# driver_board.net
KiCad netlist of a schematic drawn in EAGLE
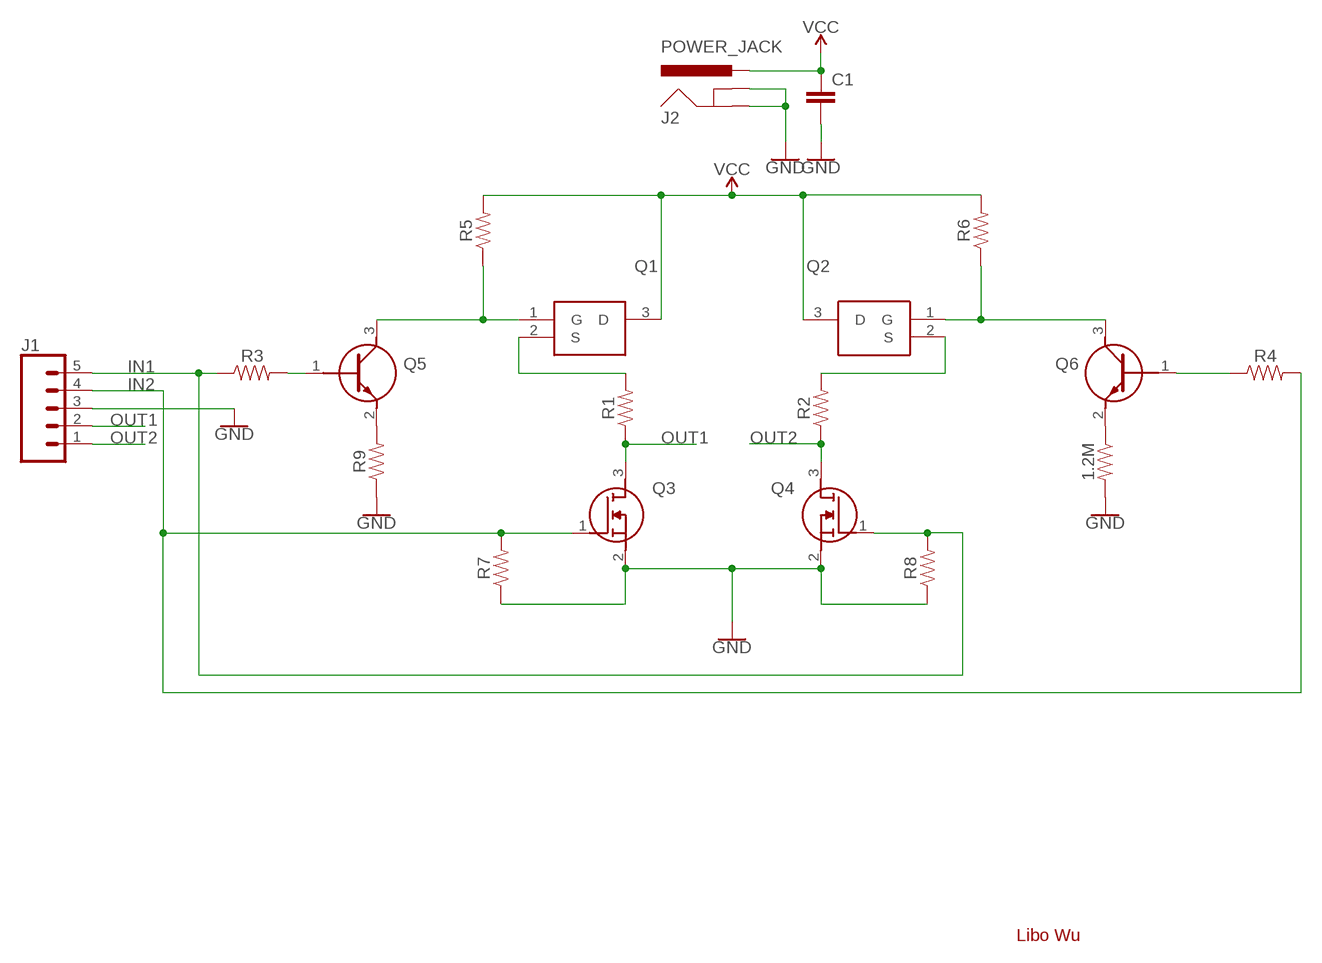
[diagram p0: schematic, sheet 1]

(export (version "E")
  (design (tool "Eeschema 10.0.6"))
  (components
    (comp (ref "C1")
      (value "10nF")
      (footprint "eagle-import:0603")
      (libsource (lib "eagle-import") (part "10NF-0603-50V-10%"))
    )
    (comp (ref "J1")
      (value "CONN_05")
      (footprint "eagle-import:1X05")
      (libsource (lib "eagle-import") (part "CONN_05"))
    )
    (comp (ref "J2")
      (value "POWER_JACK")
      (footprint "eagle-import:POWER_JACK_PTH")
      (libsource (lib "eagle-import") (part "POWER_JACK"))
    )
    (comp (ref "Q1")
      (value "IRLML6401TRPBF")
      (footprint "eagle-import:SOT95P237X112-3N")
      (fields (field (name "MOUSER_PART_NUMBER") "942-IRLML6401TRPBF"))
      (libsource (lib "eagle-import") (part "IRLML6401TRPBF"))
    )
    (comp (ref "Q2")
      (value "IRLML6401TRPBF")
      (footprint "eagle-import:SOT95P237X112-3N")
      (fields (field (name "MOUSER_PART_NUMBER") "942-IRLML6401TRPBF"))
      (libsource (lib "eagle-import") (part "IRLML6401TRPBF"))
    )
    (comp (ref "Q3")
      (value "IRLML2502TRPBF")
      (footprint "eagle-import:SOT95P237X112-3N")
      (fields (field (name "MOUSER_PART_NUMBER") "942-IRLML2502TRPBF"))
      (libsource (lib "eagle-import") (part "IRLML2502TRPBF"))
    )
    (comp (ref "Q4")
      (value "IRLML2502TRPBF")
      (footprint "eagle-import:SOT95P237X112-3N")
      (fields (field (name "MOUSER_PART_NUMBER") "942-IRLML2502TRPBF"))
      (libsource (lib "eagle-import") (part "IRLML2502TRPBF"))
    )
    (comp (ref "Q5")
      (value "BCW66HQTA")
      (footprint "eagle-import:FMMT619TA")
      (fields (field (name "MOUSER_PART_NUMBER") "621-BCW66HQTA"))
      (libsource (lib "eagle-import") (part "BCW66HQTA"))
    )
    (comp (ref "Q6")
      (value "BCW66HQTA")
      (footprint "eagle-import:FMMT619TA")
      (fields (field (name "MOUSER_PART_NUMBER") "621-BCW66HQTA"))
      (libsource (lib "eagle-import") (part "BCW66HQTA"))
    )
    (comp (ref "R1")
      (value "1.2M")
      (footprint "eagle-import:0603")
      (libsource (lib "eagle-import") (part "1.2MOHM-0603-1/10W-1%"))
    )
    (comp (ref "R2")
      (value "1.2M")
      (footprint "eagle-import:0603")
      (libsource (lib "eagle-import") (part "1.2MOHM-0603-1/10W-1%"))
    )
    (comp (ref "R3")
      (value "1.2M")
      (footprint "eagle-import:0603")
      (libsource (lib "eagle-import") (part "1.2MOHM-0603-1/10W-1%"))
    )
    (comp (ref "R4")
      (value "1.2M")
      (footprint "eagle-import:0603")
      (libsource (lib "eagle-import") (part "1.2MOHM-0603-1/10W-1%"))
    )
    (comp (ref "R5")
      (value "1.2M")
      (footprint "eagle-import:0603")
      (libsource (lib "eagle-import") (part "1.2MOHM-0603-1/10W-1%"))
    )
    (comp (ref "R6")
      (value "1.2M")
      (footprint "eagle-import:0603")
      (libsource (lib "eagle-import") (part "1.2MOHM-0603-1/10W-1%"))
    )
    (comp (ref "R7")
      (value "1.2M")
      (footprint "eagle-import:0603")
      (libsource (lib "eagle-import") (part "1.2MOHM-0603-1/10W-1%"))
    )
    (comp (ref "R8")
      (value "1.2M")
      (footprint "eagle-import:0603")
      (libsource (lib "eagle-import") (part "1.2MOHM-0603-1/10W-1%"))
    )
    (comp (ref "R9")
      (value "1.2M")
      (footprint "eagle-import:0603")
      (libsource (lib "eagle-import") (part "1.2MOHM-0603-1/10W-1%"))
    )
    (comp (ref "R10")
      (value "1.2M")
      (footprint "eagle-import:0603")
      (libsource (lib "eagle-import") (part "1.2MOHM-0603-1/10W-1%"))
    )
  )
  (nets
    (net (code "1") (name "/IN1") (class "Default")
      (node (ref "J1") (pin "5") (pinfunction "5_5") (pintype "passive"))
      (node (ref "Q4") (pin "1") (pinfunction "G_1") (pintype "bidirectional"))
      (node (ref "R3") (pin "1") (pinfunction "1_1") (pintype "passive"))
      (node (ref "R8") (pin "2") (pinfunction "2_2") (pintype "passive"))
    )
    (net (code "2") (name "/IN2") (class "Default")
      (node (ref "J1") (pin "4") (pinfunction "4_4") (pintype "passive"))
      (node (ref "Q3") (pin "1") (pinfunction "G_1") (pintype "bidirectional"))
      (node (ref "R4") (pin "2") (pinfunction "2_2") (pintype "passive"))
      (node (ref "R7") (pin "2") (pinfunction "2_2") (pintype "passive"))
    )
    (net (code "3") (name "/OUT1") (class "Default")
      (node (ref "J1") (pin "2") (pinfunction "2_2") (pintype "passive"))
      (node (ref "Q3") (pin "3") (pinfunction "D_3") (pintype "bidirectional"))
      (node (ref "R1") (pin "1") (pinfunction "1_1") (pintype "passive"))
    )
    (net (code "4") (name "/OUT2") (class "Default")
      (node (ref "J1") (pin "1") (pinfunction "1_1") (pintype "passive"))
      (node (ref "Q4") (pin "3") (pinfunction "D_3") (pintype "bidirectional"))
      (node (ref "R2") (pin "1") (pinfunction "1_1") (pintype "passive"))
    )
    (net (code "5") (name "GND") (class "Default")
      (node (ref "C1") (pin "2") (pinfunction "2_2") (pintype "passive"))
      (node (ref "J1") (pin "3") (pinfunction "3_3") (pintype "passive"))
      (node (ref "J2") (pin "GND") (pinfunction "GND_GND") (pintype "bidirectional"))
      (node (ref "J2") (pin "GNDBREAK") (pinfunction "GNDBREAK_GNDBREAK") (pintype "bidirectional"))
      (node (ref "Q3") (pin "2") (pinfunction "S_2") (pintype "bidirectional"))
      (node (ref "Q4") (pin "2") (pinfunction "S_2") (pintype "bidirectional"))
      (node (ref "R10") (pin "2") (pinfunction "2_2") (pintype "passive"))
      (node (ref "R7") (pin "1") (pinfunction "1_1") (pintype "passive"))
      (node (ref "R8") (pin "1") (pinfunction "1_1") (pintype "passive"))
      (node (ref "R9") (pin "1") (pinfunction "1_1") (pintype "passive"))
    )
    (net (code "6") (name "Net-(Q1-G)") (class "Default")
      (node (ref "Q1") (pin "1") (pinfunction "G_1") (pintype "bidirectional"))
      (node (ref "Q5") (pin "3") (pinfunction "C_3") (pintype "bidirectional"))
      (node (ref "R5") (pin "1") (pinfunction "1_1") (pintype "passive"))
    )
    (net (code "7") (name "Net-(Q1-S)") (class "Default")
      (node (ref "Q1") (pin "2") (pinfunction "S_2") (pintype "bidirectional"))
      (node (ref "R1") (pin "2") (pinfunction "2_2") (pintype "passive"))
    )
    (net (code "8") (name "Net-(Q2-G)") (class "Default")
      (node (ref "Q2") (pin "1") (pinfunction "G_1") (pintype "bidirectional"))
      (node (ref "Q6") (pin "3") (pinfunction "C_3") (pintype "bidirectional"))
      (node (ref "R6") (pin "1") (pinfunction "1_1") (pintype "passive"))
    )
    (net (code "9") (name "Net-(Q2-S)") (class "Default")
      (node (ref "Q2") (pin "2") (pinfunction "S_2") (pintype "bidirectional"))
      (node (ref "R2") (pin "2") (pinfunction "2_2") (pintype "passive"))
    )
    (net (code "10") (name "Net-(Q5-B)") (class "Default")
      (node (ref "Q5") (pin "1") (pinfunction "B_1") (pintype "bidirectional"))
      (node (ref "R3") (pin "2") (pinfunction "2_2") (pintype "passive"))
    )
    (net (code "11") (name "Net-(Q5-E)") (class "Default")
      (node (ref "Q5") (pin "2") (pinfunction "E_2") (pintype "bidirectional"))
      (node (ref "R9") (pin "2") (pinfunction "2_2") (pintype "passive"))
    )
    (net (code "12") (name "Net-(Q6-B)") (class "Default")
      (node (ref "Q6") (pin "1") (pinfunction "B_1") (pintype "bidirectional"))
      (node (ref "R4") (pin "1") (pinfunction "1_1") (pintype "passive"))
    )
    (net (code "13") (name "Net-(Q6-E)") (class "Default")
      (node (ref "Q6") (pin "2") (pinfunction "E_2") (pintype "bidirectional"))
      (node (ref "R10") (pin "1") (pinfunction "1_1") (pintype "passive"))
    )
    (net (code "14") (name "VCC") (class "Default")
      (node (ref "C1") (pin "1") (pinfunction "1_1") (pintype "passive"))
      (node (ref "J2") (pin "PWR") (pinfunction "PWR_PWR") (pintype "bidirectional"))
      (node (ref "Q1") (pin "3") (pinfunction "D_3") (pintype "bidirectional"))
      (node (ref "Q2") (pin "3") (pinfunction "D_3") (pintype "bidirectional"))
      (node (ref "R5") (pin "2") (pinfunction "2_2") (pintype "passive"))
      (node (ref "R6") (pin "2") (pinfunction "2_2") (pintype "passive"))
    )
  )
)
